# 2021_Annisa-Skripsi.net
KiCad netlist of a schematic drawn in EAGLE
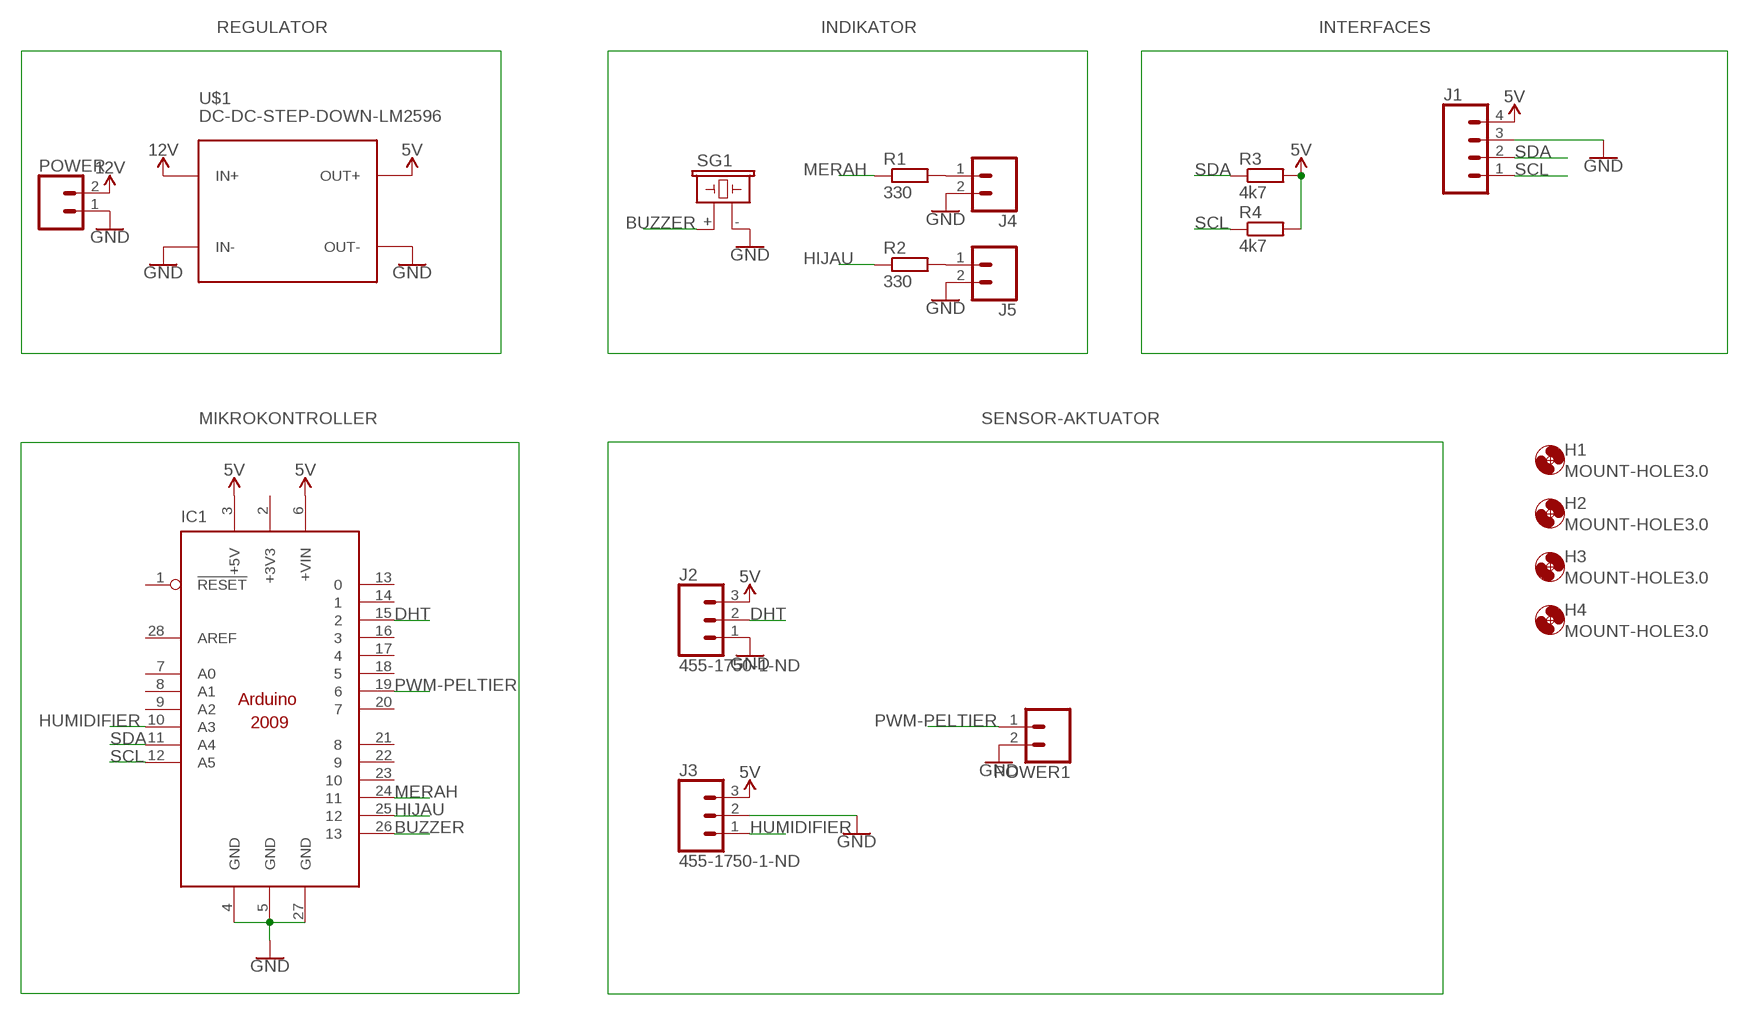
[diagram p0: schematic, sheet 1]

(export (version "E")
  (design (tool "Eeschema 10.0.6"))
  (components
    (comp (ref "H1")
      (value "MOUNT-HOLE3.0")
      (footprint "eagle-import:3,0")
      (libsource (lib "eagle-import") (part "MOUNT-HOLE3.0"))
    )
    (comp (ref "H2")
      (value "MOUNT-HOLE3.0")
      (footprint "eagle-import:3,0")
      (libsource (lib "eagle-import") (part "MOUNT-HOLE3.0"))
    )
    (comp (ref "H3")
      (value "MOUNT-HOLE3.0")
      (footprint "eagle-import:3,0")
      (libsource (lib "eagle-import") (part "MOUNT-HOLE3.0"))
    )
    (comp (ref "H4")
      (value "MOUNT-HOLE3.0")
      (footprint "eagle-import:3,0")
      (libsource (lib "eagle-import") (part "MOUNT-HOLE3.0"))
    )
    (comp (ref "IC1")
      (value "ARDUINO2009_10")
      (footprint "eagle-import:ARDUINO2009")
      (libsource (lib "eagle-import") (part "ARDUINO2009_10"))
    )
    (comp (ref "J1")
      (value "CONN_04PTH")
      (footprint "eagle-import:1X04")
      (libsource (lib "eagle-import") (part "CONN_04PTH"))
    )
    (comp (ref "J2")
      (value "455-1750-1-ND")
      (footprint "eagle-import:1X03")
      (libsource (lib "eagle-import") (part "CONN_03"))
    )
    (comp (ref "J3")
      (value "455-1750-1-ND")
      (footprint "eagle-import:1X03")
      (libsource (lib "eagle-import") (part "CONN_03"))
    )
    (comp (ref "J4")
      (value "CONN_02")
      (footprint "eagle-import:1X02")
      (libsource (lib "eagle-import") (part "CONN_02"))
    )
    (comp (ref "J5")
      (value "CONN_02")
      (footprint "eagle-import:1X02")
      (libsource (lib "eagle-import") (part "CONN_02"))
    )
    (comp (ref "POWER")
      (value "CONN_025MM")
      (footprint "eagle-import:SCREWTERMINAL-5MM-2")
      (libsource (lib "eagle-import") (part "CONN_025MM"))
    )
    (comp (ref "POWER1")
      (value "CONN_025MM")
      (footprint "eagle-import:SCREWTERMINAL-5MM-2")
      (libsource (lib "eagle-import") (part "CONN_025MM"))
    )
    (comp (ref "R1")
      (value "330")
      (footprint "eagle-import:0207_7")
      (libsource (lib "eagle-import") (part "R-EU_0207/7"))
    )
    (comp (ref "R2")
      (value "330")
      (footprint "eagle-import:0207_7")
      (libsource (lib "eagle-import") (part "R-EU_0207/7"))
    )
    (comp (ref "R3")
      (value "4k7")
      (footprint "eagle-import:0207_7")
      (libsource (lib "eagle-import") (part "R-EU_0207/7"))
    )
    (comp (ref "R4")
      (value "4k7")
      (footprint "eagle-import:0207_7")
      (libsource (lib "eagle-import") (part "R-EU_0207/7"))
    )
    (comp (ref "SG1")
      (value "F/CM12P")
      (footprint "eagle-import:F_CM12P")
      (libsource (lib "eagle-import") (part "F/CM12P"))
    )
    (comp (ref "U$1")
      (value "DC-DC-STEP-DOWN-LM2596")
      (footprint "eagle-import:DC-DC-STEP-DOWN-LM2596")
      (libsource (lib "eagle-import") (part "DC-DC-STEP-DOWN-LM2596"))
    )
  )
  (nets
    (net (code "1") (name "/+3V3") (class "Default")
      (node (ref "IC1") (pin "2") (pinfunction "+3V3_2") (pintype "power_in"))
    )
    (net (code "2") (name "/BUZZER") (class "Default")
      (node (ref "IC1") (pin "26") (pinfunction "13_26") (pintype "bidirectional"))
      (node (ref "SG1") (pin "+") (pinfunction "1_+") (pintype "passive"))
    )
    (net (code "3") (name "/DHT") (class "Default")
      (node (ref "IC1") (pin "15") (pinfunction "2_15") (pintype "bidirectional"))
      (node (ref "J2") (pin "2") (pinfunction "2_2") (pintype "passive"))
    )
    (net (code "4") (name "/HIJAU") (class "Default")
      (node (ref "IC1") (pin "25") (pinfunction "12_25") (pintype "bidirectional"))
      (node (ref "R2") (pin "1") (pinfunction "1_1") (pintype "passive"))
    )
    (net (code "5") (name "/HUMIDIFIER") (class "Default")
      (node (ref "IC1") (pin "10") (pinfunction "A3_10") (pintype "bidirectional"))
      (node (ref "J3") (pin "1") (pinfunction "1_1") (pintype "passive"))
    )
    (net (code "8") (name "/MERAH") (class "Default")
      (node (ref "IC1") (pin "24") (pinfunction "11_24") (pintype "bidirectional"))
      (node (ref "R1") (pin "1") (pinfunction "1_1") (pintype "passive"))
    )
    (net (code "10") (name "/PWM-PELTIER") (class "Default")
      (node (ref "IC1") (pin "19") (pinfunction "6_19") (pintype "bidirectional"))
      (node (ref "POWER1") (pin "1") (pinfunction "1_1") (pintype "passive"))
    )
    (net (code "12") (name "/SCL") (class "Default")
      (node (ref "IC1") (pin "12") (pinfunction "A5_12") (pintype "bidirectional"))
      (node (ref "J1") (pin "1") (pinfunction "1_1") (pintype "passive"))
      (node (ref "R4") (pin "1") (pinfunction "1_1") (pintype "passive"))
    )
    (net (code "13") (name "/SDA") (class "Default")
      (node (ref "IC1") (pin "11") (pinfunction "A4_11") (pintype "bidirectional"))
      (node (ref "J1") (pin "2") (pinfunction "2_2") (pintype "passive"))
      (node (ref "R3") (pin "1") (pinfunction "1_1") (pintype "passive"))
    )
    (net (code "15") (name "5V") (class "Default")
      (node (ref "IC1") (pin "3") (pinfunction "+5V_3") (pintype "power_in"))
      (node (ref "IC1") (pin "6") (pinfunction "+VIN_6") (pintype "bidirectional"))
      (node (ref "J1") (pin "4") (pinfunction "4_4") (pintype "passive"))
      (node (ref "J2") (pin "3") (pinfunction "3_3") (pintype "passive"))
      (node (ref "J3") (pin "3") (pinfunction "3_3") (pintype "passive"))
      (node (ref "R3") (pin "2") (pinfunction "2_2") (pintype "passive"))
      (node (ref "R4") (pin "2") (pinfunction "2_2") (pintype "passive"))
      (node (ref "U$1") (pin "OUT+") (pinfunction "OUT+_OUT+") (pintype "bidirectional"))
    )
    (net (code "16") (name "12V") (class "Default")
      (node (ref "POWER") (pin "2") (pinfunction "2_2") (pintype "passive"))
      (node (ref "U$1") (pin "IN+") (pinfunction "IN+_IN+") (pintype "bidirectional"))
    )
    (net (code "17") (name "GND") (class "Default")
      (node (ref "IC1") (pin "27") (pinfunction "GND_27") (pintype "power_in"))
      (node (ref "IC1") (pin "4") (pinfunction "GND_4") (pintype "power_in"))
      (node (ref "IC1") (pin "5") (pinfunction "GND_5") (pintype "power_in"))
      (node (ref "J1") (pin "3") (pinfunction "3_3") (pintype "passive"))
      (node (ref "J2") (pin "1") (pinfunction "1_1") (pintype "passive"))
      (node (ref "J3") (pin "2") (pinfunction "2_2") (pintype "passive"))
      (node (ref "J4") (pin "2") (pinfunction "2_2") (pintype "passive"))
      (node (ref "J5") (pin "2") (pinfunction "2_2") (pintype "passive"))
      (node (ref "POWER") (pin "1") (pinfunction "1_1") (pintype "passive"))
      (node (ref "POWER1") (pin "2") (pinfunction "2_2") (pintype "passive"))
      (node (ref "SG1") (pin "-") (pinfunction "2_-") (pintype "passive"))
      (node (ref "U$1") (pin "IN-") (pinfunction "IN-_IN-") (pintype "bidirectional"))
      (node (ref "U$1") (pin "OUT-") (pinfunction "OUT-_OUT-") (pintype "bidirectional"))
    )
    (net (code "18") (name "Net-(J4-Pad1)") (class "Default")
      (node (ref "J4") (pin "1") (pinfunction "1_1") (pintype "passive"))
      (node (ref "R1") (pin "2") (pinfunction "2_2") (pintype "passive"))
    )
    (net (code "19") (name "Net-(J5-Pad1)") (class "Default")
      (node (ref "J5") (pin "1") (pinfunction "1_1") (pintype "passive"))
      (node (ref "R2") (pin "2") (pinfunction "2_2") (pintype "passive"))
    )
    (net (code "20") (name "unconnected-(IC1-0-Pad13)") (class "Default")
      (node (ref "IC1") (pin "13") (pinfunction "0_13") (pintype "bidirectional"))
    )
    (net (code "21") (name "unconnected-(IC1-1-Pad14)") (class "Default")
      (node (ref "IC1") (pin "14") (pinfunction "1_14") (pintype "bidirectional"))
    )
    (net (code "22") (name "unconnected-(IC1-3-Pad16)") (class "Default")
      (node (ref "IC1") (pin "16") (pinfunction "3_16") (pintype "bidirectional"))
    )
    (net (code "23") (name "unconnected-(IC1-4-Pad17)") (class "Default")
      (node (ref "IC1") (pin "17") (pinfunction "4_17") (pintype "bidirectional"))
    )
    (net (code "24") (name "unconnected-(IC1-5-Pad18)") (class "Default")
      (node (ref "IC1") (pin "18") (pinfunction "5_18") (pintype "bidirectional"))
    )
    (net (code "25") (name "unconnected-(IC1-7-Pad20)") (class "Default")
      (node (ref "IC1") (pin "20") (pinfunction "7_20") (pintype "bidirectional"))
    )
    (net (code "26") (name "unconnected-(IC1-8-Pad21)") (class "Default")
      (node (ref "IC1") (pin "21") (pinfunction "8_21") (pintype "bidirectional"))
    )
    (net (code "27") (name "unconnected-(IC1-9-Pad22)") (class "Default")
      (node (ref "IC1") (pin "22") (pinfunction "9_22") (pintype "bidirectional"))
    )
    (net (code "28") (name "unconnected-(IC1-10-Pad23)") (class "Default")
      (node (ref "IC1") (pin "23") (pinfunction "10_23") (pintype "bidirectional"))
    )
    (net (code "29") (name "unconnected-(IC1-A0-Pad7)") (class "Default")
      (node (ref "IC1") (pin "7") (pinfunction "A0_7") (pintype "bidirectional"))
    )
    (net (code "30") (name "unconnected-(IC1-A1-Pad8)") (class "Default")
      (node (ref "IC1") (pin "8") (pinfunction "A1_8") (pintype "bidirectional"))
    )
    (net (code "31") (name "unconnected-(IC1-A2-Pad9)") (class "Default")
      (node (ref "IC1") (pin "9") (pinfunction "A2_9") (pintype "bidirectional"))
    )
    (net (code "32") (name "unconnected-(IC1-AREF-Pad28)") (class "Default")
      (node (ref "IC1") (pin "28") (pinfunction "AREF_28") (pintype "bidirectional"))
    )
    (net (code "33") (name "unconnected-(IC1-~{RESET}-Pad1)") (class "Default")
      (node (ref "IC1") (pin "1") (pinfunction "~{RESET}_1") (pintype "bidirectional"))
    )
  )
)
